# BOWIE_CONNECTORS.net
KiCad netlist of a schematic drawn in Altium Designer
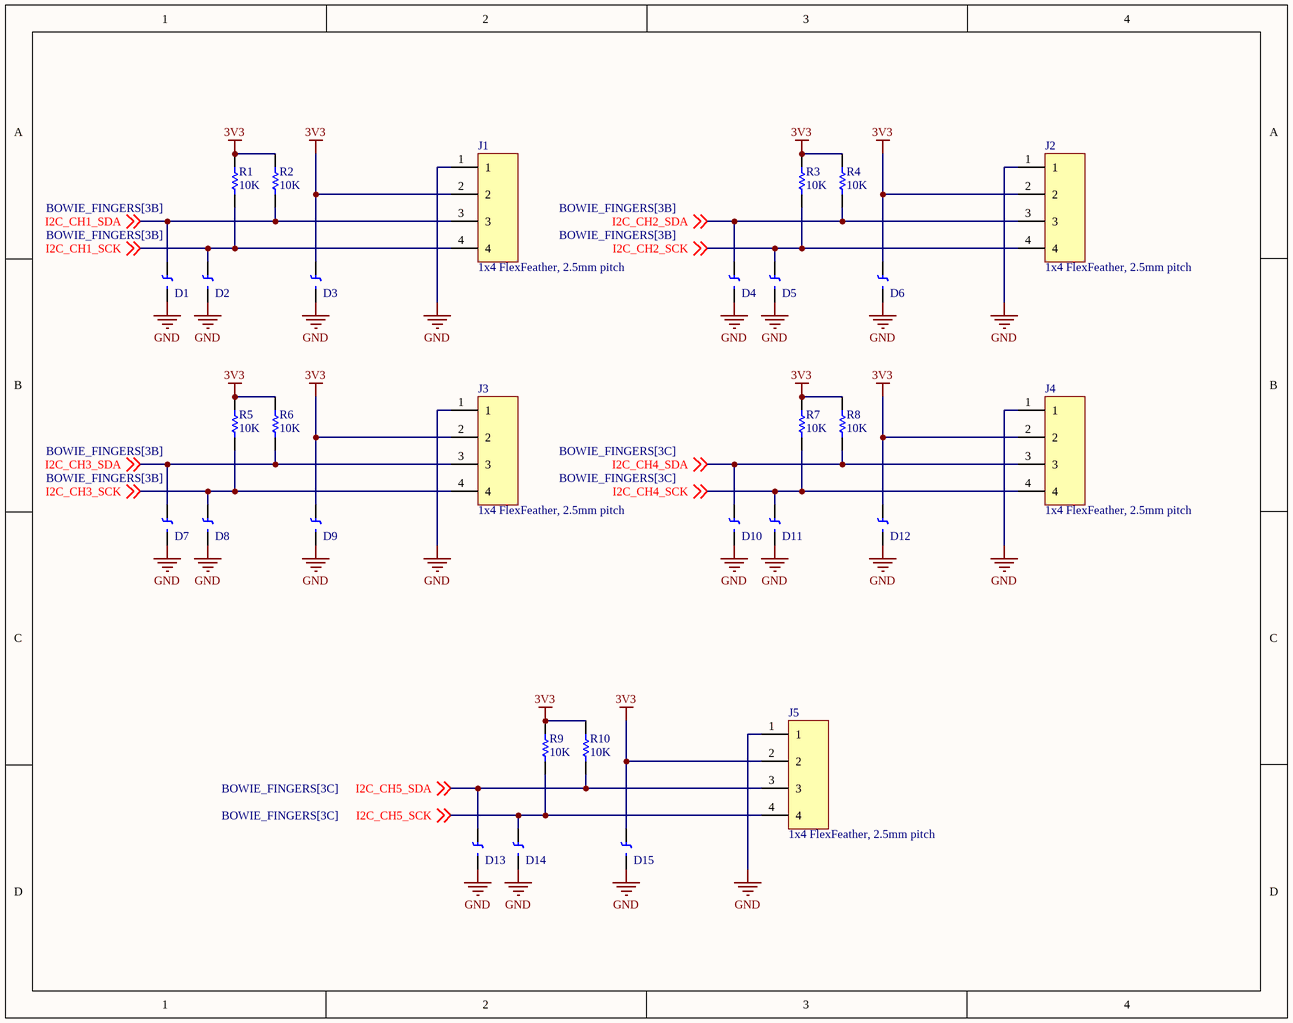
[diagram p0: BOWIE_CONNECTORS.SchDoc]

(export (version "E")
  (design (tool "Eeschema 10.0.6"))
  (components
    (comp (ref "D1")
      (value "TI_ESD351DPYR")
      (footprint "FP-DPY0002A-MFG")
      (description "DIODE, TVS, UNIDIR, 3.6VRWM, 4.5VBR, 6.5VCL, 16A, 1.8PF, X1SON-2")
      (fields
        (field (name "MANUFACTURER") "Texas Instruments")
        (field (name "MANUFACTURER PART NUMBER") "ESD351DPYR")
      )
      (libsource (lib "Miscellaneous Devices") (part "Diode_300mil_Zener"))
    )
    (comp (ref "D2")
      (value "TI_ESD351DPYR")
      (footprint "FP-DPY0002A-MFG")
      (description "DIODE, TVS, UNIDIR, 3.6VRWM, 4.5VBR, 6.5VCL, 16A, 1.8PF, X1SON-2")
      (fields
        (field (name "MANUFACTURER") "Texas Instruments")
        (field (name "MANUFACTURER PART NUMBER") "ESD351DPYR")
      )
      (libsource (lib "Miscellaneous Devices") (part "Diode_300mil_Zener"))
    )
    (comp (ref "D3")
      (value "TI_ESD351DPYR")
      (footprint "FP-DPY0002A-MFG")
      (description "DIODE, TVS, UNIDIR, 3.6VRWM, 4.5VBR, 6.5VCL, 16A, 1.8PF, X1SON-2")
      (fields
        (field (name "MANUFACTURER") "Texas Instruments")
        (field (name "MANUFACTURER PART NUMBER") "ESD351DPYR")
      )
      (libsource (lib "Miscellaneous Devices") (part "Diode_300mil_Zener"))
    )
    (comp (ref "D4")
      (value "TI_ESD351DPYR")
      (footprint "FP-DPY0002A-MFG")
      (description "DIODE, TVS, UNIDIR, 3.6VRWM, 4.5VBR, 6.5VCL, 16A, 1.8PF, X1SON-2")
      (fields
        (field (name "MANUFACTURER") "Texas Instruments")
        (field (name "MANUFACTURER PART NUMBER") "ESD351DPYR")
      )
      (libsource (lib "Miscellaneous Devices") (part "Diode_300mil_Zener"))
    )
    (comp (ref "D5")
      (value "TI_ESD351DPYR")
      (footprint "FP-DPY0002A-MFG")
      (description "DIODE, TVS, UNIDIR, 3.6VRWM, 4.5VBR, 6.5VCL, 16A, 1.8PF, X1SON-2")
      (fields
        (field (name "MANUFACTURER") "Texas Instruments")
        (field (name "MANUFACTURER PART NUMBER") "ESD351DPYR")
      )
      (libsource (lib "Miscellaneous Devices") (part "Diode_300mil_Zener"))
    )
    (comp (ref "D6")
      (value "TI_ESD351DPYR")
      (footprint "FP-DPY0002A-MFG")
      (description "DIODE, TVS, UNIDIR, 3.6VRWM, 4.5VBR, 6.5VCL, 16A, 1.8PF, X1SON-2")
      (fields
        (field (name "MANUFACTURER") "Texas Instruments")
        (field (name "MANUFACTURER PART NUMBER") "ESD351DPYR")
      )
      (libsource (lib "Miscellaneous Devices") (part "Diode_300mil_Zener"))
    )
    (comp (ref "D7")
      (value "TI_ESD351DPYR")
      (footprint "FP-DPY0002A-MFG")
      (description "DIODE, TVS, UNIDIR, 3.6VRWM, 4.5VBR, 6.5VCL, 16A, 1.8PF, X1SON-2")
      (fields
        (field (name "MANUFACTURER") "Texas Instruments")
        (field (name "MANUFACTURER PART NUMBER") "ESD351DPYR")
      )
      (libsource (lib "Miscellaneous Devices") (part "Diode_300mil_Zener"))
    )
    (comp (ref "D8")
      (value "TI_ESD351DPYR")
      (footprint "FP-DPY0002A-MFG")
      (description "DIODE, TVS, UNIDIR, 3.6VRWM, 4.5VBR, 6.5VCL, 16A, 1.8PF, X1SON-2")
      (fields
        (field (name "MANUFACTURER") "Texas Instruments")
        (field (name "MANUFACTURER PART NUMBER") "ESD351DPYR")
      )
      (libsource (lib "Miscellaneous Devices") (part "Diode_300mil_Zener"))
    )
    (comp (ref "D9")
      (value "TI_ESD351DPYR")
      (footprint "FP-DPY0002A-MFG")
      (description "DIODE, TVS, UNIDIR, 3.6VRWM, 4.5VBR, 6.5VCL, 16A, 1.8PF, X1SON-2")
      (fields
        (field (name "MANUFACTURER") "Texas Instruments")
        (field (name "MANUFACTURER PART NUMBER") "ESD351DPYR")
      )
      (libsource (lib "Miscellaneous Devices") (part "Diode_300mil_Zener"))
    )
    (comp (ref "D10")
      (value "TI_ESD351DPYR")
      (footprint "FP-DPY0002A-MFG")
      (description "DIODE, TVS, UNIDIR, 3.6VRWM, 4.5VBR, 6.5VCL, 16A, 1.8PF, X1SON-2")
      (fields
        (field (name "MANUFACTURER") "Texas Instruments")
        (field (name "MANUFACTURER PART NUMBER") "ESD351DPYR")
      )
      (libsource (lib "Miscellaneous Devices") (part "Diode_300mil_Zener"))
    )
    (comp (ref "D11")
      (value "TI_ESD351DPYR")
      (footprint "FP-DPY0002A-MFG")
      (description "DIODE, TVS, UNIDIR, 3.6VRWM, 4.5VBR, 6.5VCL, 16A, 1.8PF, X1SON-2")
      (fields
        (field (name "MANUFACTURER") "Texas Instruments")
        (field (name "MANUFACTURER PART NUMBER") "ESD351DPYR")
      )
      (libsource (lib "Miscellaneous Devices") (part "Diode_300mil_Zener"))
    )
    (comp (ref "D12")
      (value "TI_ESD351DPYR")
      (footprint "FP-DPY0002A-MFG")
      (description "DIODE, TVS, UNIDIR, 3.6VRWM, 4.5VBR, 6.5VCL, 16A, 1.8PF, X1SON-2")
      (fields
        (field (name "MANUFACTURER") "Texas Instruments")
        (field (name "MANUFACTURER PART NUMBER") "ESD351DPYR")
      )
      (libsource (lib "Miscellaneous Devices") (part "Diode_300mil_Zener"))
    )
    (comp (ref "D13")
      (value "TI_ESD351DPYR")
      (footprint "FP-DPY0002A-MFG")
      (description "DIODE, TVS, UNIDIR, 3.6VRWM, 4.5VBR, 6.5VCL, 16A, 1.8PF, X1SON-2")
      (fields
        (field (name "MANUFACTURER") "Texas Instruments")
        (field (name "MANUFACTURER PART NUMBER") "ESD351DPYR")
      )
      (libsource (lib "Miscellaneous Devices") (part "Diode_300mil_Zener"))
    )
    (comp (ref "D14")
      (value "TI_ESD351DPYR")
      (footprint "FP-DPY0002A-MFG")
      (description "DIODE, TVS, UNIDIR, 3.6VRWM, 4.5VBR, 6.5VCL, 16A, 1.8PF, X1SON-2")
      (fields
        (field (name "MANUFACTURER") "Texas Instruments")
        (field (name "MANUFACTURER PART NUMBER") "ESD351DPYR")
      )
      (libsource (lib "Miscellaneous Devices") (part "Diode_300mil_Zener"))
    )
    (comp (ref "D15")
      (value "TI_ESD351DPYR")
      (footprint "FP-DPY0002A-MFG")
      (description "DIODE, TVS, UNIDIR, 3.6VRWM, 4.5VBR, 6.5VCL, 16A, 1.8PF, X1SON-2")
      (fields
        (field (name "MANUFACTURER") "Texas Instruments")
        (field (name "MANUFACTURER PART NUMBER") "ESD351DPYR")
      )
      (libsource (lib "Miscellaneous Devices") (part "Diode_300mil_Zener"))
    )
    (comp (ref "J1")
      (value "1x4 FlexFeather, 2.5mm pitch")
      (footprint "FlexFeather_2.5mm_5mm_4pos")
      (fields (field (name "INTERNAL PART NUMBER") "XXX-XXXXX-XX"))
      (libsource (lib "846-02445-01_SCH_FlexFeather") (part "FlexFeather_2.5mm_5mm_4pos"))
    )
    (comp (ref "J2")
      (value "1x4 FlexFeather, 2.5mm pitch")
      (footprint "FlexFeather_2.5mm_5mm_4pos")
      (fields (field (name "INTERNAL PART NUMBER") "XXX-XXXXX-XX"))
      (libsource (lib "846-02445-01_SCH_FlexFeather") (part "FlexFeather_2.5mm_5mm_4pos"))
    )
    (comp (ref "J3")
      (value "1x4 FlexFeather, 2.5mm pitch")
      (footprint "FlexFeather_2.5mm_5mm_4pos")
      (fields (field (name "INTERNAL PART NUMBER") "XXX-XXXXX-XX"))
      (libsource (lib "846-02445-01_SCH_FlexFeather") (part "FlexFeather_2.5mm_5mm_4pos"))
    )
    (comp (ref "J4")
      (value "1x4 FlexFeather, 2.5mm pitch")
      (footprint "FlexFeather_2.5mm_5mm_4pos")
      (fields (field (name "INTERNAL PART NUMBER") "XXX-XXXXX-XX"))
      (libsource (lib "846-02445-01_SCH_FlexFeather") (part "FlexFeather_2.5mm_5mm_4pos"))
    )
    (comp (ref "J5")
      (value "1x4 FlexFeather, 2.5mm pitch")
      (footprint "FlexFeather_2.5mm_5mm_4pos")
      (fields (field (name "INTERNAL PART NUMBER") "XXX-XXXXX-XX"))
      (libsource (lib "846-02445-01_SCH_FlexFeather") (part "FlexFeather_2.5mm_5mm_4pos"))
    )
    (comp (ref "R1")
      (value "10K")
      (footprint "RESC1005X40X25NL05T05")
      (description "Chip Resistor, 1 KOhm, +/- 1%, 100 mW, -55 to 155 degC, 0402 (1005 Metric), RoHS, Tape and Reel")
      (fields (field (name "PARTNUMBER") "ERJ-2RKF1001X") (field (name "MANUFACTURER") "Basic Passives"))
      (libsource (lib "Altium Content Vault") (part "RES-2"))
    )
    (comp (ref "R2")
      (value "10K")
      (footprint "RESC1005X40X25NL05T05")
      (description "Chip Resistor, 1 KOhm, +/- 1%, 100 mW, -55 to 155 degC, 0402 (1005 Metric), RoHS, Tape and Reel")
      (fields (field (name "PARTNUMBER") "ERJ-2RKF1001X") (field (name "MANUFACTURER") "Basic Passives"))
      (libsource (lib "Altium Content Vault") (part "RES-2"))
    )
    (comp (ref "R3")
      (value "10K")
      (footprint "RESC1005X40X25NL05T05")
      (description "Chip Resistor, 1 KOhm, +/- 1%, 100 mW, -55 to 155 degC, 0402 (1005 Metric), RoHS, Tape and Reel")
      (fields (field (name "PARTNUMBER") "ERJ-2RKF1001X") (field (name "MANUFACTURER") "Basic Passives"))
      (libsource (lib "Altium Content Vault") (part "RES-2"))
    )
    (comp (ref "R4")
      (value "10K")
      (footprint "RESC1005X40X25NL05T05")
      (description "Chip Resistor, 1 KOhm, +/- 1%, 100 mW, -55 to 155 degC, 0402 (1005 Metric), RoHS, Tape and Reel")
      (fields (field (name "PARTNUMBER") "ERJ-2RKF1001X") (field (name "MANUFACTURER") "Basic Passives"))
      (libsource (lib "Altium Content Vault") (part "RES-2"))
    )
    (comp (ref "R5")
      (value "10K")
      (footprint "RESC1005X40X25NL05T05")
      (description "Chip Resistor, 1 KOhm, +/- 1%, 100 mW, -55 to 155 degC, 0402 (1005 Metric), RoHS, Tape and Reel")
      (fields (field (name "PARTNUMBER") "ERJ-2RKF1001X") (field (name "MANUFACTURER") "Basic Passives"))
      (libsource (lib "Altium Content Vault") (part "RES-2"))
    )
    (comp (ref "R6")
      (value "10K")
      (footprint "RESC1005X40X25NL05T05")
      (description "Chip Resistor, 1 KOhm, +/- 1%, 100 mW, -55 to 155 degC, 0402 (1005 Metric), RoHS, Tape and Reel")
      (fields (field (name "PARTNUMBER") "ERJ-2RKF1001X") (field (name "MANUFACTURER") "Basic Passives"))
      (libsource (lib "Altium Content Vault") (part "RES-2"))
    )
    (comp (ref "R7")
      (value "10K")
      (footprint "RESC1005X40X25NL05T05")
      (description "Chip Resistor, 1 KOhm, +/- 1%, 100 mW, -55 to 155 degC, 0402 (1005 Metric), RoHS, Tape and Reel")
      (fields (field (name "PARTNUMBER") "ERJ-2RKF1001X") (field (name "MANUFACTURER") "Basic Passives"))
      (libsource (lib "Altium Content Vault") (part "RES-2"))
    )
    (comp (ref "R8")
      (value "10K")
      (footprint "RESC1005X40X25NL05T05")
      (description "Chip Resistor, 1 KOhm, +/- 1%, 100 mW, -55 to 155 degC, 0402 (1005 Metric), RoHS, Tape and Reel")
      (fields (field (name "PARTNUMBER") "ERJ-2RKF1001X") (field (name "MANUFACTURER") "Basic Passives"))
      (libsource (lib "Altium Content Vault") (part "RES-2"))
    )
    (comp (ref "R9")
      (value "10K")
      (footprint "RESC1005X40X25NL05T05")
      (description "Chip Resistor, 1 KOhm, +/- 1%, 100 mW, -55 to 155 degC, 0402 (1005 Metric), RoHS, Tape and Reel")
      (fields (field (name "PARTNUMBER") "ERJ-2RKF1001X") (field (name "MANUFACTURER") "Basic Passives"))
      (libsource (lib "Altium Content Vault") (part "RES-2"))
    )
    (comp (ref "R10")
      (value "10K")
      (footprint "RESC1005X40X25NL05T05")
      (description "Chip Resistor, 1 KOhm, +/- 1%, 100 mW, -55 to 155 degC, 0402 (1005 Metric), RoHS, Tape and Reel")
      (fields (field (name "PARTNUMBER") "ERJ-2RKF1001X") (field (name "MANUFACTURER") "Basic Passives"))
      (libsource (lib "Altium Content Vault") (part "RES-2"))
    )
  )
  (nets
    (net (code "1") (name "3V3") (class "Default")
      (node (ref "D12") (pin "2") (pinfunction "Cathode_2") (pintype "passive"))
      (node (ref "D15") (pin "2") (pinfunction "Cathode_2") (pintype "passive"))
      (node (ref "D3") (pin "2") (pinfunction "Cathode_2") (pintype "passive"))
      (node (ref "D6") (pin "2") (pinfunction "Cathode_2") (pintype "passive"))
      (node (ref "D9") (pin "2") (pinfunction "Cathode_2") (pintype "passive"))
      (node (ref "J1") (pin "2") (pinfunction "2_2") (pintype "passive"))
      (node (ref "J2") (pin "2") (pinfunction "2_2") (pintype "passive"))
      (node (ref "J3") (pin "2") (pinfunction "2_2") (pintype "passive"))
      (node (ref "J4") (pin "2") (pinfunction "2_2") (pintype "passive"))
      (node (ref "J5") (pin "2") (pinfunction "2_2") (pintype "passive"))
      (node (ref "R1") (pin "2") (pinfunction "2_2") (pintype "passive"))
      (node (ref "R10") (pin "2") (pinfunction "2_2") (pintype "passive"))
      (node (ref "R2") (pin "2") (pinfunction "2_2") (pintype "passive"))
      (node (ref "R3") (pin "2") (pinfunction "2_2") (pintype "passive"))
      (node (ref "R4") (pin "2") (pinfunction "2_2") (pintype "passive"))
      (node (ref "R5") (pin "2") (pinfunction "2_2") (pintype "passive"))
      (node (ref "R6") (pin "2") (pinfunction "2_2") (pintype "passive"))
      (node (ref "R7") (pin "2") (pinfunction "2_2") (pintype "passive"))
      (node (ref "R8") (pin "2") (pinfunction "2_2") (pintype "passive"))
      (node (ref "R9") (pin "2") (pinfunction "2_2") (pintype "passive"))
    )
    (net (code "2") (name "GND") (class "Default")
      (node (ref "D1") (pin "1") (pinfunction "Anode_1") (pintype "passive"))
      (node (ref "D10") (pin "1") (pinfunction "Anode_1") (pintype "passive"))
      (node (ref "D11") (pin "1") (pinfunction "Anode_1") (pintype "passive"))
      (node (ref "D12") (pin "1") (pinfunction "Anode_1") (pintype "passive"))
      (node (ref "D13") (pin "1") (pinfunction "Anode_1") (pintype "passive"))
      (node (ref "D14") (pin "1") (pinfunction "Anode_1") (pintype "passive"))
      (node (ref "D15") (pin "1") (pinfunction "Anode_1") (pintype "passive"))
      (node (ref "D2") (pin "1") (pinfunction "Anode_1") (pintype "passive"))
      (node (ref "D3") (pin "1") (pinfunction "Anode_1") (pintype "passive"))
      (node (ref "D4") (pin "1") (pinfunction "Anode_1") (pintype "passive"))
      (node (ref "D5") (pin "1") (pinfunction "Anode_1") (pintype "passive"))
      (node (ref "D6") (pin "1") (pinfunction "Anode_1") (pintype "passive"))
      (node (ref "D7") (pin "1") (pinfunction "Anode_1") (pintype "passive"))
      (node (ref "D8") (pin "1") (pinfunction "Anode_1") (pintype "passive"))
      (node (ref "D9") (pin "1") (pinfunction "Anode_1") (pintype "passive"))
      (node (ref "J1") (pin "1") (pinfunction "1_1") (pintype "passive"))
      (node (ref "J2") (pin "1") (pinfunction "1_1") (pintype "passive"))
      (node (ref "J3") (pin "1") (pinfunction "1_1") (pintype "passive"))
      (node (ref "J4") (pin "1") (pinfunction "1_1") (pintype "passive"))
      (node (ref "J5") (pin "1") (pinfunction "1_1") (pintype "passive"))
    )
    (net (code "3") (name "I2C_CH1_SCK") (class "Default")
      (node (ref "D2") (pin "2") (pinfunction "Cathode_2") (pintype "passive"))
      (node (ref "J1") (pin "4") (pinfunction "4_4") (pintype "passive"))
      (node (ref "R1") (pin "1") (pinfunction "1_1") (pintype "passive"))
    )
    (net (code "4") (name "I2C_CH1_SDA") (class "Default")
      (node (ref "D1") (pin "2") (pinfunction "Cathode_2") (pintype "passive"))
      (node (ref "J1") (pin "3") (pinfunction "3_3") (pintype "passive"))
      (node (ref "R2") (pin "1") (pinfunction "1_1") (pintype "passive"))
    )
    (net (code "5") (name "I2C_CH2_SCK") (class "Default")
      (node (ref "D5") (pin "2") (pinfunction "Cathode_2") (pintype "passive"))
      (node (ref "J2") (pin "4") (pinfunction "4_4") (pintype "passive"))
      (node (ref "R3") (pin "1") (pinfunction "1_1") (pintype "passive"))
    )
    (net (code "6") (name "I2C_CH2_SDA") (class "Default")
      (node (ref "D4") (pin "2") (pinfunction "Cathode_2") (pintype "passive"))
      (node (ref "J2") (pin "3") (pinfunction "3_3") (pintype "passive"))
      (node (ref "R4") (pin "1") (pinfunction "1_1") (pintype "passive"))
    )
    (net (code "7") (name "I2C_CH3_SCK") (class "Default")
      (node (ref "D8") (pin "2") (pinfunction "Cathode_2") (pintype "passive"))
      (node (ref "J3") (pin "4") (pinfunction "4_4") (pintype "passive"))
      (node (ref "R5") (pin "1") (pinfunction "1_1") (pintype "passive"))
    )
    (net (code "8") (name "I2C_CH3_SDA") (class "Default")
      (node (ref "D7") (pin "2") (pinfunction "Cathode_2") (pintype "passive"))
      (node (ref "J3") (pin "3") (pinfunction "3_3") (pintype "passive"))
      (node (ref "R6") (pin "1") (pinfunction "1_1") (pintype "passive"))
    )
    (net (code "9") (name "I2C_CH4_SCK") (class "Default")
      (node (ref "D11") (pin "2") (pinfunction "Cathode_2") (pintype "passive"))
      (node (ref "J4") (pin "4") (pinfunction "4_4") (pintype "passive"))
      (node (ref "R7") (pin "1") (pinfunction "1_1") (pintype "passive"))
    )
    (net (code "10") (name "I2C_CH4_SDA") (class "Default")
      (node (ref "D10") (pin "2") (pinfunction "Cathode_2") (pintype "passive"))
      (node (ref "J4") (pin "3") (pinfunction "3_3") (pintype "passive"))
      (node (ref "R8") (pin "1") (pinfunction "1_1") (pintype "passive"))
    )
    (net (code "11") (name "I2C_CH5_SCK") (class "Default")
      (node (ref "D14") (pin "2") (pinfunction "Cathode_2") (pintype "passive"))
      (node (ref "J5") (pin "4") (pinfunction "4_4") (pintype "passive"))
      (node (ref "R9") (pin "1") (pinfunction "1_1") (pintype "passive"))
    )
    (net (code "12") (name "I2C_CH5_SDA") (class "Default")
      (node (ref "D13") (pin "2") (pinfunction "Cathode_2") (pintype "passive"))
      (node (ref "J5") (pin "3") (pinfunction "3_3") (pintype "passive"))
      (node (ref "R10") (pin "1") (pinfunction "1_1") (pintype "passive"))
    )
  )
)
